# Con_Raspi.net
KiCad netlist of a schematic drawn in EAGLE
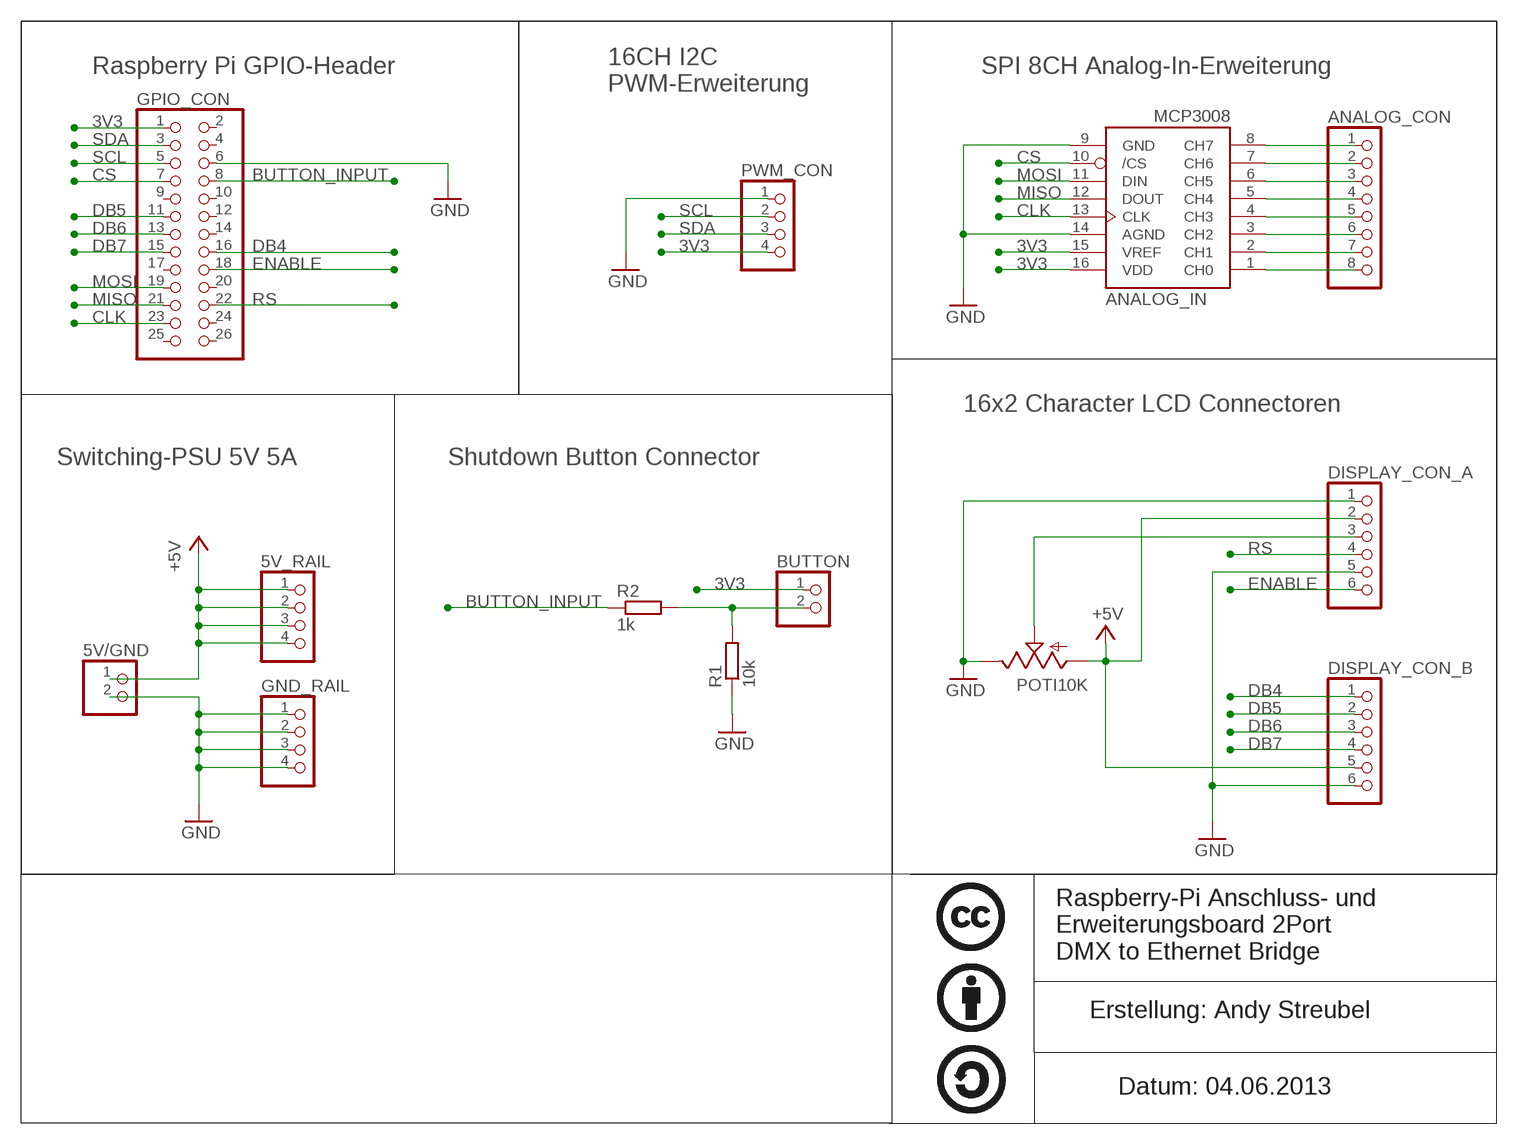
[diagram p0: schematic, sheet 1]

(export (version "E")
  (design (tool "Eeschema 10.0.6"))
  (components
    (comp (ref "5V/GND")
      (value "PINHD-1X2")
      (footprint "eagle-import:1X02")
      (libsource (lib "eagle-import") (part "PINHD-1X2"))
    )
    (comp (ref "5V_RAIL")
      (value "PINHD-1X4")
      (footprint "eagle-import:1X04")
      (libsource (lib "eagle-import") (part "PINHD-1X4"))
    )
    (comp (ref "ANALOG_CON")
      (value "PINHD-1X8")
      (footprint "eagle-import:1X08")
      (libsource (lib "eagle-import") (part "PINHD-1X8"))
    )
    (comp (ref "ANALOG_IN")
      (value "MCP3008")
      (footprint "eagle-import:DIL16")
      (libsource (lib "eagle-import") (part "MCP3008"))
    )
    (comp (ref "BUTTON")
      (value "PINHD-1X2")
      (footprint "eagle-import:1X02")
      (libsource (lib "eagle-import") (part "PINHD-1X2"))
    )
    (comp (ref "DISPLAY_CON_A")
      (value "PINHD-1X6")
      (footprint "eagle-import:1X06")
      (libsource (lib "eagle-import") (part "PINHD-1X6"))
    )
    (comp (ref "DISPLAY_CON_B")
      (value "PINHD-1X6")
      (footprint "eagle-import:1X06")
      (libsource (lib "eagle-import") (part "PINHD-1X6"))
    )
    (comp (ref "GND_RAIL")
      (value "PINHD-1X4")
      (footprint "eagle-import:1X04")
      (libsource (lib "eagle-import") (part "PINHD-1X4"))
    )
    (comp (ref "GPIO_CON")
      (value "PINHD-2X13")
      (footprint "eagle-import:2X13")
      (libsource (lib "eagle-import") (part "PINHD-2X13"))
    )
    (comp (ref "POTI10K")
      (value "TRIM")
      (footprint "eagle-import:6MM")
      (libsource (lib "eagle-import") (part "TRIM"))
    )
    (comp (ref "PWM_CON")
      (value "PINHD-1X4")
      (footprint "eagle-import:1X04")
      (libsource (lib "eagle-import") (part "PINHD-1X4"))
    )
    (comp (ref "R1")
      (value "10k")
      (footprint "eagle-import:0207_7")
      (libsource (lib "eagle-import") (part "R-EU_0207/7"))
    )
    (comp (ref "R2")
      (value "1k")
      (footprint "eagle-import:0207_7")
      (libsource (lib "eagle-import") (part "R-EU_0207/7"))
    )
  )
  (nets
    (net (code "1") (name "+5V") (class "Default")
      (node (ref "5V/GND") (pin "1") (pinfunction "1_1") (pintype "passive"))
      (node (ref "5V_RAIL") (pin "1") (pinfunction "1_1") (pintype "passive"))
      (node (ref "5V_RAIL") (pin "2") (pinfunction "2_2") (pintype "passive"))
      (node (ref "5V_RAIL") (pin "3") (pinfunction "3_3") (pintype "passive"))
      (node (ref "5V_RAIL") (pin "4") (pinfunction "4_4") (pintype "passive"))
      (node (ref "DISPLAY_CON_A") (pin "2") (pinfunction "2_2") (pintype "passive"))
      (node (ref "DISPLAY_CON_B") (pin "5") (pinfunction "5_5") (pintype "passive"))
      (node (ref "POTI10K") (pin "A") (pinfunction "A_A") (pintype "passive"))
    )
    (net (code "2") (name "/3V3") (class "Default")
      (node (ref "ANALOG_IN") (pin "15") (pinfunction "VREF_15") (pintype "input"))
      (node (ref "ANALOG_IN") (pin "16") (pinfunction "VDD_16") (pintype "power_in"))
      (node (ref "BUTTON") (pin "1") (pinfunction "1_1") (pintype "passive"))
      (node (ref "GPIO_CON") (pin "1") (pinfunction "1_1") (pintype "passive"))
      (node (ref "PWM_CON") (pin "4") (pinfunction "4_4") (pintype "passive"))
    )
    (net (code "3") (name "/BUTTON_INPUT") (class "Default")
      (node (ref "GPIO_CON") (pin "8") (pinfunction "8_8") (pintype "passive"))
      (node (ref "R2") (pin "1") (pinfunction "1_1") (pintype "passive"))
    )
    (net (code "4") (name "/CLK") (class "Default")
      (node (ref "ANALOG_IN") (pin "13") (pinfunction "CLK_13") (pintype "input"))
      (node (ref "GPIO_CON") (pin "23") (pinfunction "23_23") (pintype "passive"))
    )
    (net (code "5") (name "/CS") (class "Default")
      (node (ref "ANALOG_IN") (pin "10") (pinfunction "/CS_10") (pintype "input"))
      (node (ref "GPIO_CON") (pin "7") (pinfunction "7_7") (pintype "passive"))
    )
    (net (code "6") (name "/DB4") (class "Default")
      (node (ref "DISPLAY_CON_B") (pin "1") (pinfunction "1_1") (pintype "passive"))
      (node (ref "GPIO_CON") (pin "16") (pinfunction "16_16") (pintype "passive"))
    )
    (net (code "7") (name "/DB5") (class "Default")
      (node (ref "DISPLAY_CON_B") (pin "2") (pinfunction "2_2") (pintype "passive"))
      (node (ref "GPIO_CON") (pin "11") (pinfunction "11_11") (pintype "passive"))
    )
    (net (code "8") (name "/DB6") (class "Default")
      (node (ref "DISPLAY_CON_B") (pin "3") (pinfunction "3_3") (pintype "passive"))
      (node (ref "GPIO_CON") (pin "13") (pinfunction "13_13") (pintype "passive"))
    )
    (net (code "9") (name "/DB7") (class "Default")
      (node (ref "DISPLAY_CON_B") (pin "4") (pinfunction "4_4") (pintype "passive"))
      (node (ref "GPIO_CON") (pin "15") (pinfunction "15_15") (pintype "passive"))
    )
    (net (code "10") (name "/ENABLE") (class "Default")
      (node (ref "DISPLAY_CON_A") (pin "6") (pinfunction "6_6") (pintype "passive"))
      (node (ref "GPIO_CON") (pin "18") (pinfunction "18_18") (pintype "passive"))
    )
    (net (code "11") (name "/MISO") (class "Default")
      (node (ref "ANALOG_IN") (pin "12") (pinfunction "DOUT_12") (pintype "output"))
      (node (ref "GPIO_CON") (pin "21") (pinfunction "21_21") (pintype "passive"))
    )
    (net (code "12") (name "/MOSI") (class "Default")
      (node (ref "ANALOG_IN") (pin "11") (pinfunction "DIN_11") (pintype "input"))
      (node (ref "GPIO_CON") (pin "19") (pinfunction "19_19") (pintype "passive"))
    )
    (net (code "13") (name "/RS") (class "Default")
      (node (ref "DISPLAY_CON_A") (pin "4") (pinfunction "4_4") (pintype "passive"))
      (node (ref "GPIO_CON") (pin "22") (pinfunction "22_22") (pintype "passive"))
    )
    (net (code "14") (name "/SCL") (class "Default")
      (node (ref "GPIO_CON") (pin "5") (pinfunction "5_5") (pintype "passive"))
      (node (ref "PWM_CON") (pin "2") (pinfunction "2_2") (pintype "passive"))
    )
    (net (code "15") (name "/SDA") (class "Default")
      (node (ref "GPIO_CON") (pin "3") (pinfunction "3_3") (pintype "passive"))
      (node (ref "PWM_CON") (pin "3") (pinfunction "3_3") (pintype "passive"))
    )
    (net (code "16") (name "GND") (class "Default")
      (node (ref "5V/GND") (pin "2") (pinfunction "2_2") (pintype "passive"))
      (node (ref "ANALOG_IN") (pin "14") (pinfunction "AGND_14") (pintype "power_in"))
      (node (ref "ANALOG_IN") (pin "9") (pinfunction "GND_9") (pintype "power_in"))
      (node (ref "DISPLAY_CON_A") (pin "1") (pinfunction "1_1") (pintype "passive"))
      (node (ref "DISPLAY_CON_A") (pin "5") (pinfunction "5_5") (pintype "passive"))
      (node (ref "DISPLAY_CON_B") (pin "6") (pinfunction "6_6") (pintype "passive"))
      (node (ref "GND_RAIL") (pin "1") (pinfunction "1_1") (pintype "passive"))
      (node (ref "GND_RAIL") (pin "2") (pinfunction "2_2") (pintype "passive"))
      (node (ref "GND_RAIL") (pin "3") (pinfunction "3_3") (pintype "passive"))
      (node (ref "GND_RAIL") (pin "4") (pinfunction "4_4") (pintype "passive"))
      (node (ref "GPIO_CON") (pin "6") (pinfunction "6_6") (pintype "passive"))
      (node (ref "POTI10K") (pin "E") (pinfunction "E_E") (pintype "passive"))
      (node (ref "PWM_CON") (pin "1") (pinfunction "1_1") (pintype "passive"))
      (node (ref "R1") (pin "1") (pinfunction "1_1") (pintype "passive"))
    )
    (net (code "17") (name "Net-(ANALOG_IN-CH0)") (class "Default")
      (node (ref "ANALOG_CON") (pin "8") (pinfunction "8_8") (pintype "passive"))
      (node (ref "ANALOG_IN") (pin "1") (pinfunction "CH0_1") (pintype "input"))
    )
    (net (code "18") (name "Net-(ANALOG_IN-CH1)") (class "Default")
      (node (ref "ANALOG_CON") (pin "7") (pinfunction "7_7") (pintype "passive"))
      (node (ref "ANALOG_IN") (pin "2") (pinfunction "CH1_2") (pintype "input"))
    )
    (net (code "19") (name "Net-(ANALOG_IN-CH2)") (class "Default")
      (node (ref "ANALOG_CON") (pin "6") (pinfunction "6_6") (pintype "passive"))
      (node (ref "ANALOG_IN") (pin "3") (pinfunction "CH2_3") (pintype "input"))
    )
    (net (code "20") (name "Net-(ANALOG_IN-CH3)") (class "Default")
      (node (ref "ANALOG_CON") (pin "5") (pinfunction "5_5") (pintype "passive"))
      (node (ref "ANALOG_IN") (pin "4") (pinfunction "CH3_4") (pintype "input"))
    )
    (net (code "21") (name "Net-(ANALOG_IN-CH4)") (class "Default")
      (node (ref "ANALOG_CON") (pin "4") (pinfunction "4_4") (pintype "passive"))
      (node (ref "ANALOG_IN") (pin "5") (pinfunction "CH4_5") (pintype "input"))
    )
    (net (code "22") (name "Net-(ANALOG_IN-CH5)") (class "Default")
      (node (ref "ANALOG_CON") (pin "3") (pinfunction "3_3") (pintype "passive"))
      (node (ref "ANALOG_IN") (pin "6") (pinfunction "CH5_6") (pintype "input"))
    )
    (net (code "23") (name "Net-(ANALOG_IN-CH6)") (class "Default")
      (node (ref "ANALOG_CON") (pin "2") (pinfunction "2_2") (pintype "passive"))
      (node (ref "ANALOG_IN") (pin "7") (pinfunction "CH6_7") (pintype "input"))
    )
    (net (code "24") (name "Net-(ANALOG_IN-CH7)") (class "Default")
      (node (ref "ANALOG_CON") (pin "1") (pinfunction "1_1") (pintype "passive"))
      (node (ref "ANALOG_IN") (pin "8") (pinfunction "CH7_8") (pintype "input"))
    )
    (net (code "25") (name "Net-(BUTTON-Pad2)") (class "Default")
      (node (ref "BUTTON") (pin "2") (pinfunction "2_2") (pintype "passive"))
      (node (ref "R1") (pin "2") (pinfunction "2_2") (pintype "passive"))
      (node (ref "R2") (pin "2") (pinfunction "2_2") (pintype "passive"))
    )
    (net (code "26") (name "Net-(DISPLAY_CON_A-Pad3)") (class "Default")
      (node (ref "DISPLAY_CON_A") (pin "3") (pinfunction "3_3") (pintype "passive"))
      (node (ref "POTI10K") (pin "S") (pinfunction "S_S") (pintype "passive"))
    )
    (net (code "27") (name "unconnected-(GPIO_CON-Pad2)") (class "Default")
      (node (ref "GPIO_CON") (pin "2") (pinfunction "2_2") (pintype "passive"))
    )
    (net (code "28") (name "unconnected-(GPIO_CON-Pad4)") (class "Default")
      (node (ref "GPIO_CON") (pin "4") (pinfunction "4_4") (pintype "passive"))
    )
    (net (code "29") (name "unconnected-(GPIO_CON-Pad9)") (class "Default")
      (node (ref "GPIO_CON") (pin "9") (pinfunction "9_9") (pintype "passive"))
    )
    (net (code "30") (name "unconnected-(GPIO_CON-Pad10)") (class "Default")
      (node (ref "GPIO_CON") (pin "10") (pinfunction "10_10") (pintype "passive"))
    )
    (net (code "31") (name "unconnected-(GPIO_CON-Pad12)") (class "Default")
      (node (ref "GPIO_CON") (pin "12") (pinfunction "12_12") (pintype "passive"))
    )
    (net (code "32") (name "unconnected-(GPIO_CON-Pad14)") (class "Default")
      (node (ref "GPIO_CON") (pin "14") (pinfunction "14_14") (pintype "passive"))
    )
    (net (code "33") (name "unconnected-(GPIO_CON-Pad17)") (class "Default")
      (node (ref "GPIO_CON") (pin "17") (pinfunction "17_17") (pintype "passive"))
    )
    (net (code "34") (name "unconnected-(GPIO_CON-Pad20)") (class "Default")
      (node (ref "GPIO_CON") (pin "20") (pinfunction "20_20") (pintype "passive"))
    )
    (net (code "35") (name "unconnected-(GPIO_CON-Pad24)") (class "Default")
      (node (ref "GPIO_CON") (pin "24") (pinfunction "24_24") (pintype "passive"))
    )
    (net (code "36") (name "unconnected-(GPIO_CON-Pad25)") (class "Default")
      (node (ref "GPIO_CON") (pin "25") (pinfunction "25_25") (pintype "passive"))
    )
    (net (code "37") (name "unconnected-(GPIO_CON-Pad26)") (class "Default")
      (node (ref "GPIO_CON") (pin "26") (pinfunction "26_26") (pintype "passive"))
    )
  )
)
